# LEDResetBoardRevB.net
KiCad netlist of a schematic drawn in EAGLE
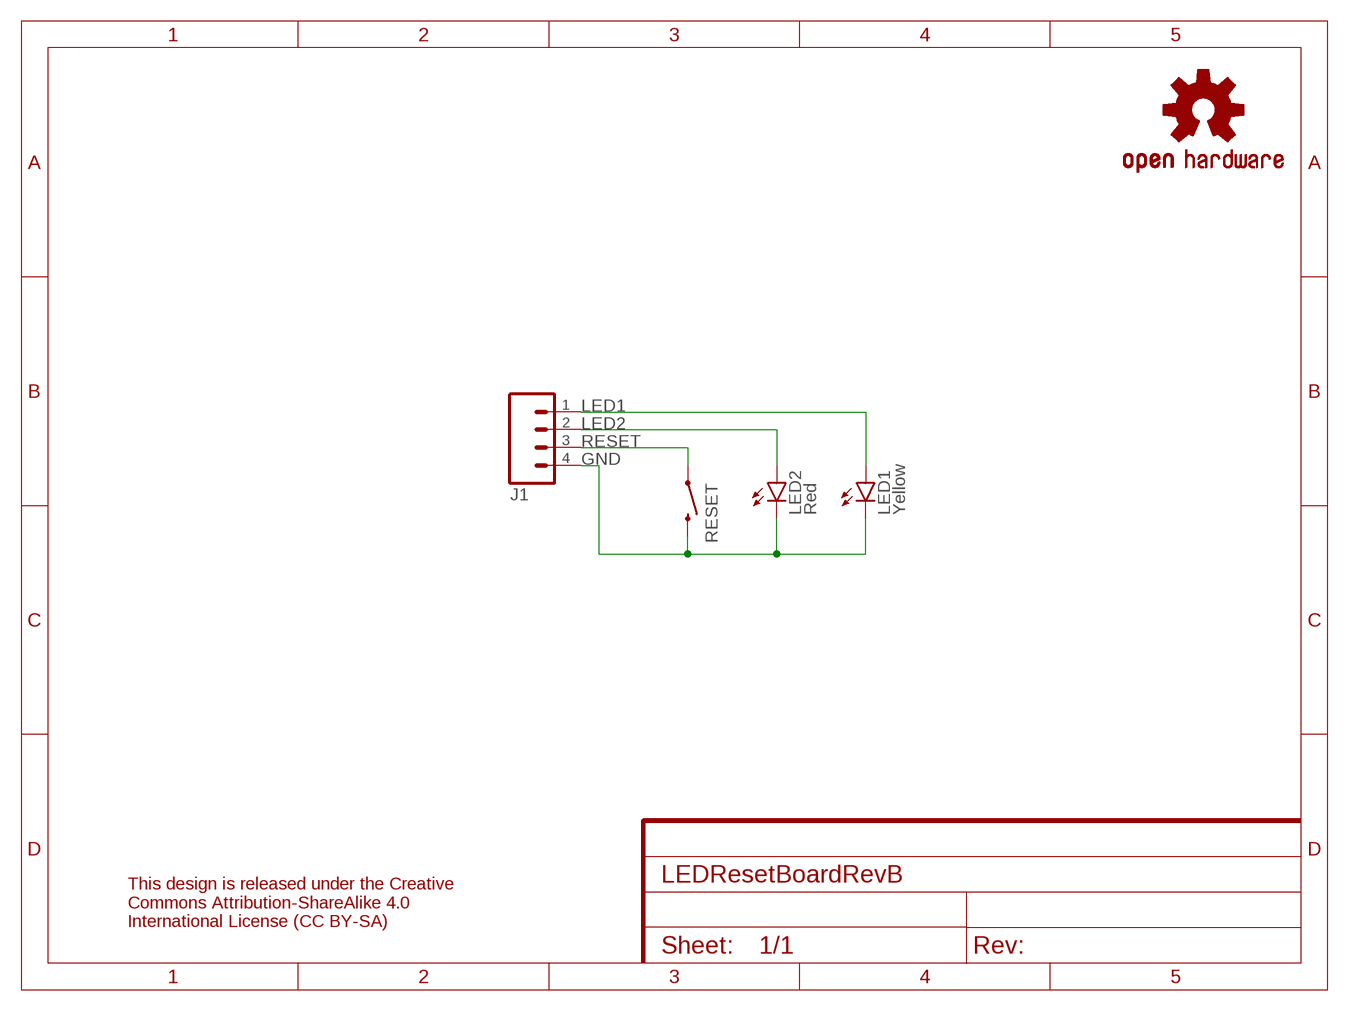
[diagram p0: schematic, sheet 1]

(export (version "E")
  (design (tool "Eeschema 10.0.6"))
  (components
    (comp (ref "J1")
      (value "M04PTH")
      (footprint "eagle-import:1X04")
      (libsource (lib "eagle-import") (part "M04PTH"))
    )
    (comp (ref "LED1")
      (value "Yellow")
      (footprint "eagle-import:LED3MM")
      (libsource (lib "eagle-import") (part "LED3MM"))
    )
    (comp (ref "LED2")
      (value "Red")
      (footprint "eagle-import:LED3MM")
      (libsource (lib "eagle-import") (part "LED3MM"))
    )
    (comp (ref "LOGO1")
      (value "OSHW-LOGOS")
      (footprint "eagle-import:OSHW-LOGO-S")
      (libsource (lib "eagle-import") (part "OSHW-LOGOS"))
    )
    (comp (ref "RESET")
      (value "SWITCH-MOMENTARY-2PTH")
      (footprint "eagle-import:TACTILE-PTH")
      (libsource (lib "eagle-import") (part "SWITCH-MOMENTARY-2PTH"))
    )
  )
  (nets
    (net (code "1") (name "/GND") (class "Default")
      (node (ref "J1") (pin "4") (pinfunction "4_4") (pintype "passive"))
      (node (ref "LED1") (pin "K") (pinfunction "C_K") (pintype "passive"))
      (node (ref "LED2") (pin "K") (pinfunction "C_K") (pintype "passive"))
      (node (ref "RESET") (pin "3") (pinfunction "2_3") (pintype "passive"))
    )
    (net (code "2") (name "/LED1") (class "Default")
      (node (ref "J1") (pin "1") (pinfunction "1_1") (pintype "passive"))
      (node (ref "LED1") (pin "A") (pinfunction "A_A") (pintype "passive"))
    )
    (net (code "3") (name "/LED2") (class "Default")
      (node (ref "J1") (pin "2") (pinfunction "2_2") (pintype "passive"))
      (node (ref "LED2") (pin "A") (pinfunction "A_A") (pintype "passive"))
    )
    (net (code "4") (name "/RESET") (class "Default")
      (node (ref "J1") (pin "3") (pinfunction "3_3") (pintype "passive"))
      (node (ref "RESET") (pin "1") (pinfunction "1_1") (pintype "passive"))
    )
  )
)
